# INA219x4_FeatherWing.net
KiCad netlist of a schematic drawn in EAGLE
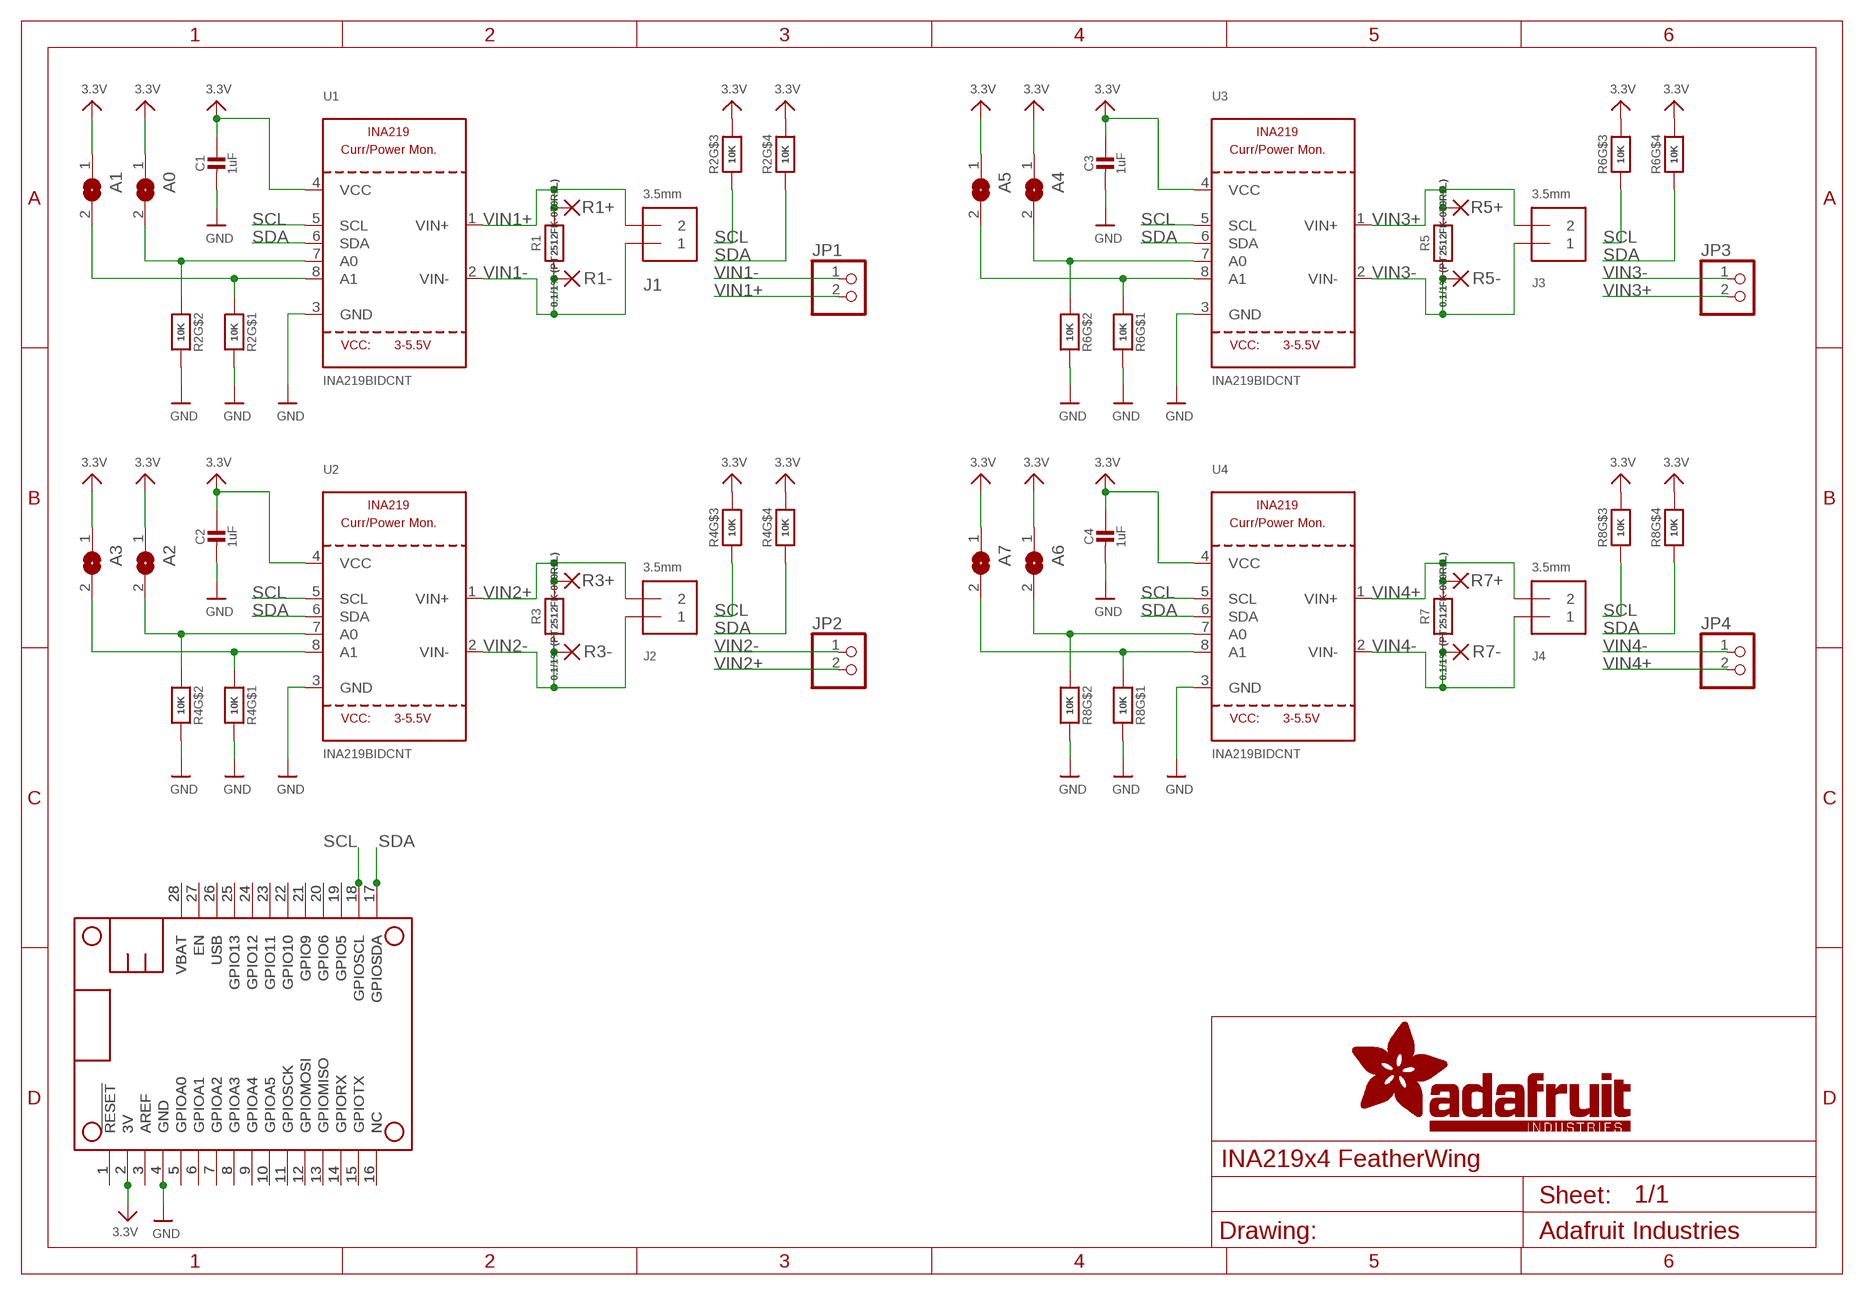
[diagram p0: schematic, sheet 1]

(export (version "E")
  (design (tool "Eeschema 10.0.6"))
  (components
    (comp (ref "A0")
      (value "SOLDERJUMPERREFLOW_NOPASTE")
      (footprint "eagle-import:SOLDERJUMPER_REFLOW_NOPASTE")
      (libsource (lib "eagle-import") (part "SOLDERJUMPERREFLOW_NOPASTE"))
    )
    (comp (ref "A1")
      (value "SOLDERJUMPERREFLOW_NOPASTE")
      (footprint "eagle-import:SOLDERJUMPER_REFLOW_NOPASTE")
      (libsource (lib "eagle-import") (part "SOLDERJUMPERREFLOW_NOPASTE"))
    )
    (comp (ref "A2")
      (value "SOLDERJUMPERREFLOW_NOPASTE")
      (footprint "eagle-import:SOLDERJUMPER_REFLOW_NOPASTE")
      (libsource (lib "eagle-import") (part "SOLDERJUMPERREFLOW_NOPASTE"))
    )
    (comp (ref "A3")
      (value "SOLDERJUMPERREFLOW_NOPASTE")
      (footprint "eagle-import:SOLDERJUMPER_REFLOW_NOPASTE")
      (libsource (lib "eagle-import") (part "SOLDERJUMPERREFLOW_NOPASTE"))
    )
    (comp (ref "A4")
      (value "SOLDERJUMPERREFLOW_NOPASTE")
      (footprint "eagle-import:SOLDERJUMPER_REFLOW_NOPASTE")
      (libsource (lib "eagle-import") (part "SOLDERJUMPERREFLOW_NOPASTE"))
    )
    (comp (ref "A5")
      (value "SOLDERJUMPERREFLOW_NOPASTE")
      (footprint "eagle-import:SOLDERJUMPER_REFLOW_NOPASTE")
      (libsource (lib "eagle-import") (part "SOLDERJUMPERREFLOW_NOPASTE"))
    )
    (comp (ref "A6")
      (value "SOLDERJUMPERREFLOW_NOPASTE")
      (footprint "eagle-import:SOLDERJUMPER_REFLOW_NOPASTE")
      (libsource (lib "eagle-import") (part "SOLDERJUMPERREFLOW_NOPASTE"))
    )
    (comp (ref "A7")
      (value "SOLDERJUMPERREFLOW_NOPASTE")
      (footprint "eagle-import:SOLDERJUMPER_REFLOW_NOPASTE")
      (libsource (lib "eagle-import") (part "SOLDERJUMPERREFLOW_NOPASTE"))
    )
    (comp (ref "C1")
      (value "1uF")
      (footprint "eagle-import:0805-NO@1")
      (libsource (lib "eagle-import") (part "CAP_CERAMIC0805-NOOUTLINE"))
    )
    (comp (ref "C2")
      (value "1uF")
      (footprint "eagle-import:0805-NO@1")
      (libsource (lib "eagle-import") (part "CAP_CERAMIC0805-NOOUTLINE"))
    )
    (comp (ref "C3")
      (value "1uF")
      (footprint "eagle-import:0805-NO@1")
      (libsource (lib "eagle-import") (part "CAP_CERAMIC0805-NOOUTLINE"))
    )
    (comp (ref "C4")
      (value "1uF")
      (footprint "eagle-import:0805-NO@1")
      (libsource (lib "eagle-import") (part "CAP_CERAMIC0805-NOOUTLINE"))
    )
    (comp (ref "J1")
      (value "3.5mm")
      (footprint "eagle-import:TERMBLOCK_1X2-3.5MM")
      (libsource (lib "eagle-import") (part "TERMBLOCK_1X2"))
    )
    (comp (ref "J2")
      (value "3.5mm")
      (footprint "eagle-import:TERMBLOCK_1X2-3.5MM")
      (libsource (lib "eagle-import") (part "TERMBLOCK_1X2"))
    )
    (comp (ref "J3")
      (value "3.5mm")
      (footprint "eagle-import:TERMBLOCK_1X2-3.5MM")
      (libsource (lib "eagle-import") (part "TERMBLOCK_1X2"))
    )
    (comp (ref "J4")
      (value "3.5mm")
      (footprint "eagle-import:TERMBLOCK_1X2-3.5MM")
      (libsource (lib "eagle-import") (part "TERMBLOCK_1X2"))
    )
    (comp (ref "JP1")
      (value "HEADER-1X2ROUND")
      (footprint "eagle-import:1X02_ROUND")
      (libsource (lib "eagle-import") (part "HEADER-1X2ROUND"))
    )
    (comp (ref "JP2")
      (value "HEADER-1X2ROUND")
      (footprint "eagle-import:1X02_ROUND")
      (libsource (lib "eagle-import") (part "HEADER-1X2ROUND"))
    )
    (comp (ref "JP3")
      (value "HEADER-1X2ROUND")
      (footprint "eagle-import:1X02_ROUND")
      (libsource (lib "eagle-import") (part "HEADER-1X2ROUND"))
    )
    (comp (ref "JP4")
      (value "HEADER-1X2ROUND")
      (footprint "eagle-import:1X02_ROUND")
      (libsource (lib "eagle-import") (part "HEADER-1X2ROUND"))
    )
    (comp (ref "MS1")
      (value "FEATHERWING_NODIM")
      (footprint "eagle-import:FEATHERWING_DIM")
      (libsource (lib "eagle-import") (part "FEATHERWING_NODIM"))
    )
    (comp (ref "MS2")
      (value "FEATHERWING_NODIM")
      (footprint "eagle-import:FEATHERWING_DIM")
      (libsource (lib "eagle-import") (part "FEATHERWING_NODIM"))
    )
    (comp (ref "R1")
      (value "0.1/1% (PT2512FK-070R1L)")
      (footprint "eagle-import:2512")
      (libsource (lib "eagle-import") (part "RESISTOR2512"))
    )
    (comp (ref "R1+")
      (value "1,6/0,9")
      (footprint "eagle-import:1,6_0,9")
      (libsource (lib "eagle-import") (part "1,6/0,9"))
    )
    (comp (ref "R1-")
      (value "1,6/0,9")
      (footprint "eagle-import:1,6_0,9")
      (libsource (lib "eagle-import") (part "1,6/0,9"))
    )
    (comp (ref "R2")
      (value "10K")
      (footprint "eagle-import:RESPACK_4X0603")
      (libsource (lib "eagle-import") (part "RESISTOR_4PACK"))
    )
    (comp (ref "R3")
      (value "0.1/1% (PT2512FK-070R1L)")
      (footprint "eagle-import:2512")
      (libsource (lib "eagle-import") (part "RESISTOR2512"))
    )
    (comp (ref "R3+")
      (value "1,6/0,9")
      (footprint "eagle-import:1,6_0,9")
      (libsource (lib "eagle-import") (part "1,6/0,9"))
    )
    (comp (ref "R3-")
      (value "1,6/0,9")
      (footprint "eagle-import:1,6_0,9")
      (libsource (lib "eagle-import") (part "1,6/0,9"))
    )
    (comp (ref "R4")
      (value "10K")
      (footprint "eagle-import:RESPACK_4X0603")
      (libsource (lib "eagle-import") (part "RESISTOR_4PACK"))
    )
    (comp (ref "R5")
      (value "0.1/1% (PT2512FK-070R1L)")
      (footprint "eagle-import:2512")
      (libsource (lib "eagle-import") (part "RESISTOR2512"))
    )
    (comp (ref "R5+")
      (value "1,6/0,9")
      (footprint "eagle-import:1,6_0,9")
      (libsource (lib "eagle-import") (part "1,6/0,9"))
    )
    (comp (ref "R5-")
      (value "1,6/0,9")
      (footprint "eagle-import:1,6_0,9")
      (libsource (lib "eagle-import") (part "1,6/0,9"))
    )
    (comp (ref "R6")
      (value "10K")
      (footprint "eagle-import:RESPACK_4X0603")
      (libsource (lib "eagle-import") (part "RESISTOR_4PACK"))
    )
    (comp (ref "R7")
      (value "0.1/1% (PT2512FK-070R1L)")
      (footprint "eagle-import:2512")
      (libsource (lib "eagle-import") (part "RESISTOR2512"))
    )
    (comp (ref "R7+")
      (value "1,6/0,9")
      (footprint "eagle-import:1,6_0,9")
      (libsource (lib "eagle-import") (part "1,6/0,9"))
    )
    (comp (ref "R7-")
      (value "1,6/0,9")
      (footprint "eagle-import:1,6_0,9")
      (libsource (lib "eagle-import") (part "1,6/0,9"))
    )
    (comp (ref "R8")
      (value "10K")
      (footprint "eagle-import:RESPACK_4X0603")
      (libsource (lib "eagle-import") (part "RESISTOR_4PACK"))
    )
    (comp (ref "U1")
      (value "INA219BIDCNT")
      (footprint "eagle-import:SOT23-8")
      (libsource (lib "eagle-import") (part "INA219"))
    )
    (comp (ref "U2")
      (value "INA219BIDCNT")
      (footprint "eagle-import:SOT23-8")
      (libsource (lib "eagle-import") (part "INA219"))
    )
    (comp (ref "U3")
      (value "INA219BIDCNT")
      (footprint "eagle-import:SOT23-8")
      (libsource (lib "eagle-import") (part "INA219"))
    )
    (comp (ref "U4")
      (value "INA219BIDCNT")
      (footprint "eagle-import:SOT23-8")
      (libsource (lib "eagle-import") (part "INA219"))
    )
  )
  (nets
    (net (code "1") (name "/SCL") (class "Default")
      (node (ref "MS1") (pin "18") (pinfunction "GPIOSCL_18") (pintype "bidirectional"))
      (node (ref "MS2") (pin "18") (pinfunction "GPIOSCL_18") (pintype "bidirectional"))
      (node (ref "R2") (pin "3") (pinfunction "1_3") (pintype "passive"))
      (node (ref "R4") (pin "3") (pinfunction "1_3") (pintype "passive"))
      (node (ref "R6") (pin "3") (pinfunction "1_3") (pintype "passive"))
      (node (ref "R8") (pin "3") (pinfunction "1_3") (pintype "passive"))
      (node (ref "U1") (pin "5") (pinfunction "SCL_5") (pintype "bidirectional"))
      (node (ref "U2") (pin "5") (pinfunction "SCL_5") (pintype "bidirectional"))
      (node (ref "U3") (pin "5") (pinfunction "SCL_5") (pintype "bidirectional"))
      (node (ref "U4") (pin "5") (pinfunction "SCL_5") (pintype "bidirectional"))
    )
    (net (code "2") (name "/SDA") (class "Default")
      (node (ref "MS1") (pin "17") (pinfunction "GPIOSDA_17") (pintype "bidirectional"))
      (node (ref "MS2") (pin "17") (pinfunction "GPIOSDA_17") (pintype "bidirectional"))
      (node (ref "R2") (pin "4") (pinfunction "1_4") (pintype "passive"))
      (node (ref "R4") (pin "4") (pinfunction "1_4") (pintype "passive"))
      (node (ref "R6") (pin "4") (pinfunction "1_4") (pintype "passive"))
      (node (ref "R8") (pin "4") (pinfunction "1_4") (pintype "passive"))
      (node (ref "U1") (pin "6") (pinfunction "SDA_6") (pintype "bidirectional"))
      (node (ref "U2") (pin "6") (pinfunction "SDA_6") (pintype "bidirectional"))
      (node (ref "U3") (pin "6") (pinfunction "SDA_6") (pintype "bidirectional"))
      (node (ref "U4") (pin "6") (pinfunction "SDA_6") (pintype "bidirectional"))
    )
    (net (code "3") (name "/VIN1+") (class "Default")
      (node (ref "J1") (pin "2") (pinfunction "2_2") (pintype "passive"))
      (node (ref "JP1") (pin "2") (pinfunction "2_2") (pintype "passive"))
      (node (ref "R1") (pin "2") (pinfunction "2_2") (pintype "passive"))
      (node (ref "R1+") (pin "1") (pinfunction "P_1") (pintype "passive"))
      (node (ref "U1") (pin "1") (pinfunction "VIN+_1") (pintype "bidirectional"))
    )
    (net (code "4") (name "/VIN1-") (class "Default")
      (node (ref "J1") (pin "1") (pinfunction "1_1") (pintype "passive"))
      (node (ref "JP1") (pin "1") (pinfunction "1_1") (pintype "passive"))
      (node (ref "R1") (pin "1") (pinfunction "1_1") (pintype "passive"))
      (node (ref "R1-") (pin "1") (pinfunction "P_1") (pintype "passive"))
      (node (ref "U1") (pin "2") (pinfunction "VIN-_2") (pintype "bidirectional"))
    )
    (net (code "5") (name "/VIN2+") (class "Default")
      (node (ref "J2") (pin "2") (pinfunction "2_2") (pintype "passive"))
      (node (ref "JP2") (pin "2") (pinfunction "2_2") (pintype "passive"))
      (node (ref "R3") (pin "2") (pinfunction "2_2") (pintype "passive"))
      (node (ref "R3+") (pin "1") (pinfunction "P_1") (pintype "passive"))
      (node (ref "U2") (pin "1") (pinfunction "VIN+_1") (pintype "bidirectional"))
    )
    (net (code "6") (name "/VIN2-") (class "Default")
      (node (ref "J2") (pin "1") (pinfunction "1_1") (pintype "passive"))
      (node (ref "JP2") (pin "1") (pinfunction "1_1") (pintype "passive"))
      (node (ref "R3") (pin "1") (pinfunction "1_1") (pintype "passive"))
      (node (ref "R3-") (pin "1") (pinfunction "P_1") (pintype "passive"))
      (node (ref "U2") (pin "2") (pinfunction "VIN-_2") (pintype "bidirectional"))
    )
    (net (code "7") (name "/VIN3+") (class "Default")
      (node (ref "J3") (pin "2") (pinfunction "2_2") (pintype "passive"))
      (node (ref "JP3") (pin "2") (pinfunction "2_2") (pintype "passive"))
      (node (ref "R5") (pin "2") (pinfunction "2_2") (pintype "passive"))
      (node (ref "R5+") (pin "1") (pinfunction "P_1") (pintype "passive"))
      (node (ref "U3") (pin "1") (pinfunction "VIN+_1") (pintype "bidirectional"))
    )
    (net (code "8") (name "/VIN3-") (class "Default")
      (node (ref "J3") (pin "1") (pinfunction "1_1") (pintype "passive"))
      (node (ref "JP3") (pin "1") (pinfunction "1_1") (pintype "passive"))
      (node (ref "R5") (pin "1") (pinfunction "1_1") (pintype "passive"))
      (node (ref "R5-") (pin "1") (pinfunction "P_1") (pintype "passive"))
      (node (ref "U3") (pin "2") (pinfunction "VIN-_2") (pintype "bidirectional"))
    )
    (net (code "9") (name "/VIN4+") (class "Default")
      (node (ref "J4") (pin "2") (pinfunction "2_2") (pintype "passive"))
      (node (ref "JP4") (pin "2") (pinfunction "2_2") (pintype "passive"))
      (node (ref "R7") (pin "2") (pinfunction "2_2") (pintype "passive"))
      (node (ref "R7+") (pin "1") (pinfunction "P_1") (pintype "passive"))
      (node (ref "U4") (pin "1") (pinfunction "VIN+_1") (pintype "bidirectional"))
    )
    (net (code "10") (name "/VIN4-") (class "Default")
      (node (ref "J4") (pin "1") (pinfunction "1_1") (pintype "passive"))
      (node (ref "JP4") (pin "1") (pinfunction "1_1") (pintype "passive"))
      (node (ref "R7") (pin "1") (pinfunction "1_1") (pintype "passive"))
      (node (ref "R7-") (pin "1") (pinfunction "P_1") (pintype "passive"))
      (node (ref "U4") (pin "2") (pinfunction "VIN-_2") (pintype "bidirectional"))
    )
    (net (code "11") (name "3.3V") (class "Default")
      (node (ref "A0") (pin "1") (pinfunction "1_1") (pintype "passive"))
      (node (ref "A1") (pin "1") (pinfunction "1_1") (pintype "passive"))
      (node (ref "A2") (pin "1") (pinfunction "1_1") (pintype "passive"))
      (node (ref "A3") (pin "1") (pinfunction "1_1") (pintype "passive"))
      (node (ref "A4") (pin "1") (pinfunction "1_1") (pintype "passive"))
      (node (ref "A5") (pin "1") (pinfunction "1_1") (pintype "passive"))
      (node (ref "A6") (pin "1") (pinfunction "1_1") (pintype "passive"))
      (node (ref "A7") (pin "1") (pinfunction "1_1") (pintype "passive"))
      (node (ref "C1") (pin "1") (pinfunction "1_1") (pintype "passive"))
      (node (ref "C2") (pin "1") (pinfunction "1_1") (pintype "passive"))
      (node (ref "C3") (pin "1") (pinfunction "1_1") (pintype "passive"))
      (node (ref "C4") (pin "1") (pinfunction "1_1") (pintype "passive"))
      (node (ref "MS1") (pin "2") (pinfunction "3V_2") (pintype "power_in"))
      (node (ref "MS2") (pin "2") (pinfunction "3V_2") (pintype "power_in"))
      (node (ref "R2") (pin "5") (pinfunction "2_5") (pintype "passive"))
      (node (ref "R2") (pin "6") (pinfunction "2_6") (pintype "passive"))
      (node (ref "R4") (pin "5") (pinfunction "2_5") (pintype "passive"))
      (node (ref "R4") (pin "6") (pinfunction "2_6") (pintype "passive"))
      (node (ref "R6") (pin "5") (pinfunction "2_5") (pintype "passive"))
      (node (ref "R6") (pin "6") (pinfunction "2_6") (pintype "passive"))
      (node (ref "R8") (pin "5") (pinfunction "2_5") (pintype "passive"))
      (node (ref "R8") (pin "6") (pinfunction "2_6") (pintype "passive"))
      (node (ref "U1") (pin "4") (pinfunction "VCC_4") (pintype "power_in"))
      (node (ref "U2") (pin "4") (pinfunction "VCC_4") (pintype "power_in"))
      (node (ref "U3") (pin "4") (pinfunction "VCC_4") (pintype "power_in"))
      (node (ref "U4") (pin "4") (pinfunction "VCC_4") (pintype "power_in"))
    )
    (net (code "12") (name "GND") (class "Default")
      (node (ref "C1") (pin "2") (pinfunction "2_2") (pintype "passive"))
      (node (ref "C2") (pin "2") (pinfunction "2_2") (pintype "passive"))
      (node (ref "C3") (pin "2") (pinfunction "2_2") (pintype "passive"))
      (node (ref "C4") (pin "2") (pinfunction "2_2") (pintype "passive"))
      (node (ref "MS1") (pin "4") (pinfunction "GND_4") (pintype "power_in"))
      (node (ref "MS2") (pin "4") (pinfunction "GND_4") (pintype "power_in"))
      (node (ref "R2") (pin "7") (pinfunction "2_7") (pintype "passive"))
      (node (ref "R2") (pin "8") (pinfunction "2_8") (pintype "passive"))
      (node (ref "R4") (pin "7") (pinfunction "2_7") (pintype "passive"))
      (node (ref "R4") (pin "8") (pinfunction "2_8") (pintype "passive"))
      (node (ref "R6") (pin "7") (pinfunction "2_7") (pintype "passive"))
      (node (ref "R6") (pin "8") (pinfunction "2_8") (pintype "passive"))
      (node (ref "R8") (pin "7") (pinfunction "2_7") (pintype "passive"))
      (node (ref "R8") (pin "8") (pinfunction "2_8") (pintype "passive"))
      (node (ref "U1") (pin "3") (pinfunction "GND_3") (pintype "power_in"))
      (node (ref "U2") (pin "3") (pinfunction "GND_3") (pintype "power_in"))
      (node (ref "U3") (pin "3") (pinfunction "GND_3") (pintype "power_in"))
      (node (ref "U4") (pin "3") (pinfunction "GND_3") (pintype "power_in"))
    )
    (net (code "13") (name "Net-(MS1-AREF)") (class "Default")
      (node (ref "MS1") (pin "3") (pinfunction "AREF_3") (pintype "passive"))
      (node (ref "MS2") (pin "3") (pinfunction "AREF_3") (pintype "passive"))
    )
    (net (code "14") (name "Net-(MS1-EN)") (class "Default")
      (node (ref "MS1") (pin "27") (pinfunction "EN_27") (pintype "passive"))
      (node (ref "MS2") (pin "27") (pinfunction "EN_27") (pintype "passive"))
    )
    (net (code "15") (name "Net-(MS1-GPIO5)") (class "Default")
      (node (ref "MS1") (pin "19") (pinfunction "GPIO5_19") (pintype "bidirectional"))
      (node (ref "MS2") (pin "19") (pinfunction "GPIO5_19") (pintype "bidirectional"))
    )
    (net (code "16") (name "Net-(MS1-GPIO6)") (class "Default")
      (node (ref "MS1") (pin "20") (pinfunction "GPIO6_20") (pintype "bidirectional"))
      (node (ref "MS2") (pin "20") (pinfunction "GPIO6_20") (pintype "bidirectional"))
    )
    (net (code "17") (name "Net-(MS1-GPIO9)") (class "Default")
      (node (ref "MS1") (pin "21") (pinfunction "GPIO9_21") (pintype "bidirectional"))
      (node (ref "MS2") (pin "21") (pinfunction "GPIO9_21") (pintype "bidirectional"))
    )
    (net (code "18") (name "Net-(MS1-GPIO10)") (class "Default")
      (node (ref "MS1") (pin "22") (pinfunction "GPIO10_22") (pintype "bidirectional"))
      (node (ref "MS2") (pin "22") (pinfunction "GPIO10_22") (pintype "bidirectional"))
    )
    (net (code "19") (name "Net-(MS1-GPIO11)") (class "Default")
      (node (ref "MS1") (pin "23") (pinfunction "GPIO11_23") (pintype "bidirectional"))
      (node (ref "MS2") (pin "23") (pinfunction "GPIO11_23") (pintype "bidirectional"))
    )
    (net (code "20") (name "Net-(MS1-GPIO12)") (class "Default")
      (node (ref "MS1") (pin "24") (pinfunction "GPIO12_24") (pintype "bidirectional"))
      (node (ref "MS2") (pin "24") (pinfunction "GPIO12_24") (pintype "bidirectional"))
    )
    (net (code "21") (name "Net-(MS1-GPIO13)") (class "Default")
      (node (ref "MS1") (pin "25") (pinfunction "GPIO13_25") (pintype "bidirectional"))
      (node (ref "MS2") (pin "25") (pinfunction "GPIO13_25") (pintype "bidirectional"))
    )
    (net (code "22") (name "Net-(MS1-GPIOA0)") (class "Default")
      (node (ref "MS1") (pin "5") (pinfunction "GPIOA0_5") (pintype "bidirectional"))
      (node (ref "MS2") (pin "5") (pinfunction "GPIOA0_5") (pintype "bidirectional"))
    )
    (net (code "23") (name "Net-(MS1-GPIOA1)") (class "Default")
      (node (ref "MS1") (pin "6") (pinfunction "GPIOA1_6") (pintype "bidirectional"))
      (node (ref "MS2") (pin "6") (pinfunction "GPIOA1_6") (pintype "bidirectional"))
    )
    (net (code "24") (name "Net-(MS1-GPIOA2)") (class "Default")
      (node (ref "MS1") (pin "7") (pinfunction "GPIOA2_7") (pintype "bidirectional"))
      (node (ref "MS2") (pin "7") (pinfunction "GPIOA2_7") (pintype "bidirectional"))
    )
    (net (code "25") (name "Net-(MS1-GPIOA3)") (class "Default")
      (node (ref "MS1") (pin "8") (pinfunction "GPIOA3_8") (pintype "bidirectional"))
      (node (ref "MS2") (pin "8") (pinfunction "GPIOA3_8") (pintype "bidirectional"))
    )
    (net (code "26") (name "Net-(MS1-GPIOA4)") (class "Default")
      (node (ref "MS1") (pin "9") (pinfunction "GPIOA4_9") (pintype "bidirectional"))
      (node (ref "MS2") (pin "9") (pinfunction "GPIOA4_9") (pintype "bidirectional"))
    )
    (net (code "27") (name "Net-(MS1-GPIOA5)") (class "Default")
      (node (ref "MS1") (pin "10") (pinfunction "GPIOA5_10") (pintype "bidirectional"))
      (node (ref "MS2") (pin "10") (pinfunction "GPIOA5_10") (pintype "bidirectional"))
    )
    (net (code "28") (name "Net-(MS1-GPIOMISO)") (class "Default")
      (node (ref "MS1") (pin "13") (pinfunction "GPIOMISO_13") (pintype "bidirectional"))
      (node (ref "MS2") (pin "13") (pinfunction "GPIOMISO_13") (pintype "bidirectional"))
    )
    (net (code "29") (name "Net-(MS1-GPIOMOSI)") (class "Default")
      (node (ref "MS1") (pin "12") (pinfunction "GPIOMOSI_12") (pintype "bidirectional"))
      (node (ref "MS2") (pin "12") (pinfunction "GPIOMOSI_12") (pintype "bidirectional"))
    )
    (net (code "30") (name "Net-(MS1-GPIORX)") (class "Default")
      (node (ref "MS1") (pin "14") (pinfunction "GPIORX_14") (pintype "bidirectional"))
      (node (ref "MS2") (pin "14") (pinfunction "GPIORX_14") (pintype "bidirectional"))
    )
    (net (code "31") (name "Net-(MS1-GPIOSCK)") (class "Default")
      (node (ref "MS1") (pin "11") (pinfunction "GPIOSCK_11") (pintype "bidirectional"))
      (node (ref "MS2") (pin "11") (pinfunction "GPIOSCK_11") (pintype "bidirectional"))
    )
    (net (code "32") (name "Net-(MS1-GPIOTX)") (class "Default")
      (node (ref "MS1") (pin "15") (pinfunction "GPIOTX_15") (pintype "bidirectional"))
      (node (ref "MS2") (pin "15") (pinfunction "GPIOTX_15") (pintype "bidirectional"))
    )
    (net (code "33") (name "Net-(MS1-NC)") (class "Default")
      (node (ref "MS1") (pin "16") (pinfunction "NC_16") (pintype "passive"))
      (node (ref "MS2") (pin "16") (pinfunction "NC_16") (pintype "passive"))
    )
    (net (code "34") (name "Net-(MS1-USB)") (class "Default")
      (node (ref "MS1") (pin "26") (pinfunction "USB_26") (pintype "power_in"))
      (node (ref "MS2") (pin "26") (pinfunction "USB_26") (pintype "power_in"))
    )
    (net (code "35") (name "Net-(MS1-VBAT)") (class "Default")
      (node (ref "MS1") (pin "28") (pinfunction "VBAT_28") (pintype "power_in"))
      (node (ref "MS2") (pin "28") (pinfunction "VBAT_28") (pintype "power_in"))
    )
    (net (code "36") (name "Net-(MS1-~{RESET})") (class "Default")
      (node (ref "MS1") (pin "1") (pinfunction "~{RESET}_1") (pintype "input"))
      (node (ref "MS2") (pin "1") (pinfunction "~{RESET}_1") (pintype "input"))
    )
    (net (code "37") (name "Net-(R2B-1)") (class "Default")
      (node (ref "A0") (pin "2") (pinfunction "2_2") (pintype "passive"))
      (node (ref "R2") (pin "2") (pinfunction "1_2") (pintype "passive"))
      (node (ref "U1") (pin "7") (pinfunction "A0_7") (pintype "bidirectional"))
    )
    (net (code "38") (name "Net-(R4B-1)") (class "Default")
      (node (ref "A2") (pin "2") (pinfunction "2_2") (pintype "passive"))
      (node (ref "R4") (pin "2") (pinfunction "1_2") (pintype "passive"))
      (node (ref "U2") (pin "7") (pinfunction "A0_7") (pintype "bidirectional"))
    )
    (net (code "39") (name "Net-(R6B-1)") (class "Default")
      (node (ref "A4") (pin "2") (pinfunction "2_2") (pintype "passive"))
      (node (ref "R6") (pin "2") (pinfunction "1_2") (pintype "passive"))
      (node (ref "U3") (pin "7") (pinfunction "A0_7") (pintype "bidirectional"))
    )
    (net (code "40") (name "Net-(R8B-1)") (class "Default")
      (node (ref "A6") (pin "2") (pinfunction "2_2") (pintype "passive"))
      (node (ref "R8") (pin "2") (pinfunction "1_2") (pintype "passive"))
      (node (ref "U4") (pin "7") (pinfunction "A0_7") (pintype "bidirectional"))
    )
    (net (code "41") (name "Net-(U1-A1)") (class "Default")
      (node (ref "A1") (pin "2") (pinfunction "2_2") (pintype "passive"))
      (node (ref "R2") (pin "1") (pinfunction "1_1") (pintype "passive"))
      (node (ref "U1") (pin "8") (pinfunction "A1_8") (pintype "bidirectional"))
    )
    (net (code "42") (name "Net-(U2-A1)") (class "Default")
      (node (ref "A3") (pin "2") (pinfunction "2_2") (pintype "passive"))
      (node (ref "R4") (pin "1") (pinfunction "1_1") (pintype "passive"))
      (node (ref "U2") (pin "8") (pinfunction "A1_8") (pintype "bidirectional"))
    )
    (net (code "43") (name "Net-(U3-A1)") (class "Default")
      (node (ref "A5") (pin "2") (pinfunction "2_2") (pintype "passive"))
      (node (ref "R6") (pin "1") (pinfunction "1_1") (pintype "passive"))
      (node (ref "U3") (pin "8") (pinfunction "A1_8") (pintype "bidirectional"))
    )
    (net (code "44") (name "Net-(U4-A1)") (class "Default")
      (node (ref "A7") (pin "2") (pinfunction "2_2") (pintype "passive"))
      (node (ref "R8") (pin "1") (pinfunction "1_1") (pintype "passive"))
      (node (ref "U4") (pin "8") (pinfunction "A1_8") (pintype "bidirectional"))
    )
  )
)
